# version1.net
KiCad netlist of a schematic drawn in EAGLE
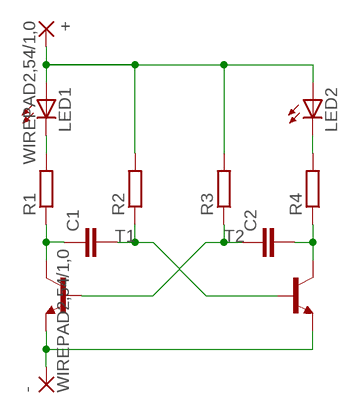
[diagram p0: schematic, sheet 1]

(export (version "E")
  (design (tool "Eeschema 10.0.6"))
  (components
    (comp (ref "+")
      (value "WIREPAD2,54/1,0")
      (footprint "eagle-import:2,54_1,0")
      (libsource (lib "eagle-import") (part "WIREPAD2,54/1,0"))
    )
    (comp (ref "-")
      (value "WIREPAD2,54/1,0")
      (footprint "eagle-import:2,54_1,0")
      (libsource (lib "eagle-import") (part "WIREPAD2,54/1,0"))
    )
    (comp (ref "C1")
      (value "C-EUC0603")
      (footprint "eagle-import:C0603")
      (libsource (lib "eagle-import") (part "C-EUC0603"))
    )
    (comp (ref "C2")
      (value "C-EUC0603")
      (footprint "eagle-import:C0603")
      (libsource (lib "eagle-import") (part "C-EUC0603"))
    )
    (comp (ref "LED1")
      (value "LEDSML0603")
      (footprint "eagle-import:SML0603")
      (libsource (lib "eagle-import") (part "LEDSML0603"))
    )
    (comp (ref "LED2")
      (value "LEDSML0603")
      (footprint "eagle-import:SML0603")
      (libsource (lib "eagle-import") (part "LEDSML0603"))
    )
    (comp (ref "R1")
      (value "R-EU_R0603")
      (footprint "eagle-import:R0603")
      (libsource (lib "eagle-import") (part "R-EU_R0603"))
    )
    (comp (ref "R2")
      (value "R-EU_R0603")
      (footprint "eagle-import:R0603")
      (libsource (lib "eagle-import") (part "R-EU_R0603"))
    )
    (comp (ref "R3")
      (value "R-EU_R0603")
      (footprint "eagle-import:R0603")
      (libsource (lib "eagle-import") (part "R-EU_R0603"))
    )
    (comp (ref "R4")
      (value "R-EU_R0603")
      (footprint "eagle-import:R0603")
      (libsource (lib "eagle-import") (part "R-EU_R0603"))
    )
    (comp (ref "T1")
      (value "MMBT2222ALT1-NPN-SOT23-BEC")
      (footprint "eagle-import:SOT23-BEC")
      (libsource (lib "eagle-import") (part "-NPN-SOT23-BECMMBT2222ALT1"))
    )
    (comp (ref "T2")
      (value "MMBT2222ALT1-NPN-SOT23-BEC")
      (footprint "eagle-import:SOT23-BEC")
      (libsource (lib "eagle-import") (part "-NPN-SOT23-BECMMBT2222ALT1"))
    )
  )
  (nets
    (net (code "1") (name "Net-(+-P)") (class "Default")
      (node (ref "+") (pin "1") (pinfunction "P_1") (pintype "passive"))
      (node (ref "LED1") (pin "A") (pinfunction "A_A") (pintype "passive"))
      (node (ref "LED2") (pin "A") (pinfunction "A_A") (pintype "passive"))
      (node (ref "R2") (pin "2") (pinfunction "2_2") (pintype "passive"))
      (node (ref "R3") (pin "2") (pinfunction "2_2") (pintype "passive"))
    )
    (net (code "2") (name "Net-(--P)") (class "Default")
      (node (ref "-") (pin "1") (pinfunction "P_1") (pintype "passive"))
      (node (ref "T1") (pin "E") (pinfunction "E_E") (pintype "passive"))
      (node (ref "T2") (pin "E") (pinfunction "E_E") (pintype "passive"))
    )
    (net (code "3") (name "Net-(C1-Pad1)") (class "Default")
      (node (ref "C1") (pin "1") (pinfunction "1_1") (pintype "passive"))
      (node (ref "R1") (pin "1") (pinfunction "1_1") (pintype "passive"))
      (node (ref "T1") (pin "C") (pinfunction "C_C") (pintype "passive"))
    )
    (net (code "4") (name "Net-(C1-Pad2)") (class "Default")
      (node (ref "C1") (pin "2") (pinfunction "2_2") (pintype "passive"))
      (node (ref "R2") (pin "1") (pinfunction "1_1") (pintype "passive"))
      (node (ref "T2") (pin "B") (pinfunction "B_B") (pintype "passive"))
    )
    (net (code "5") (name "Net-(C2-Pad1)") (class "Default")
      (node (ref "C2") (pin "1") (pinfunction "1_1") (pintype "passive"))
      (node (ref "R3") (pin "1") (pinfunction "1_1") (pintype "passive"))
      (node (ref "T1") (pin "B") (pinfunction "B_B") (pintype "passive"))
    )
    (net (code "6") (name "Net-(C2-Pad2)") (class "Default")
      (node (ref "C2") (pin "2") (pinfunction "2_2") (pintype "passive"))
      (node (ref "R4") (pin "1") (pinfunction "1_1") (pintype "passive"))
      (node (ref "T2") (pin "C") (pinfunction "C_C") (pintype "passive"))
    )
    (net (code "7") (name "Net-(LED1-PadC)") (class "Default")
      (node (ref "LED1") (pin "C") (pinfunction "C_C") (pintype "passive"))
      (node (ref "R1") (pin "2") (pinfunction "2_2") (pintype "passive"))
    )
    (net (code "8") (name "Net-(LED2-PadC)") (class "Default")
      (node (ref "LED2") (pin "C") (pinfunction "C_C") (pintype "passive"))
      (node (ref "R4") (pin "2") (pinfunction "2_2") (pintype "passive"))
    )
  )
)
